# 2022-06-23_LN2_Autofill_Controller.net
KiCad netlist of a schematic drawn in EAGLE
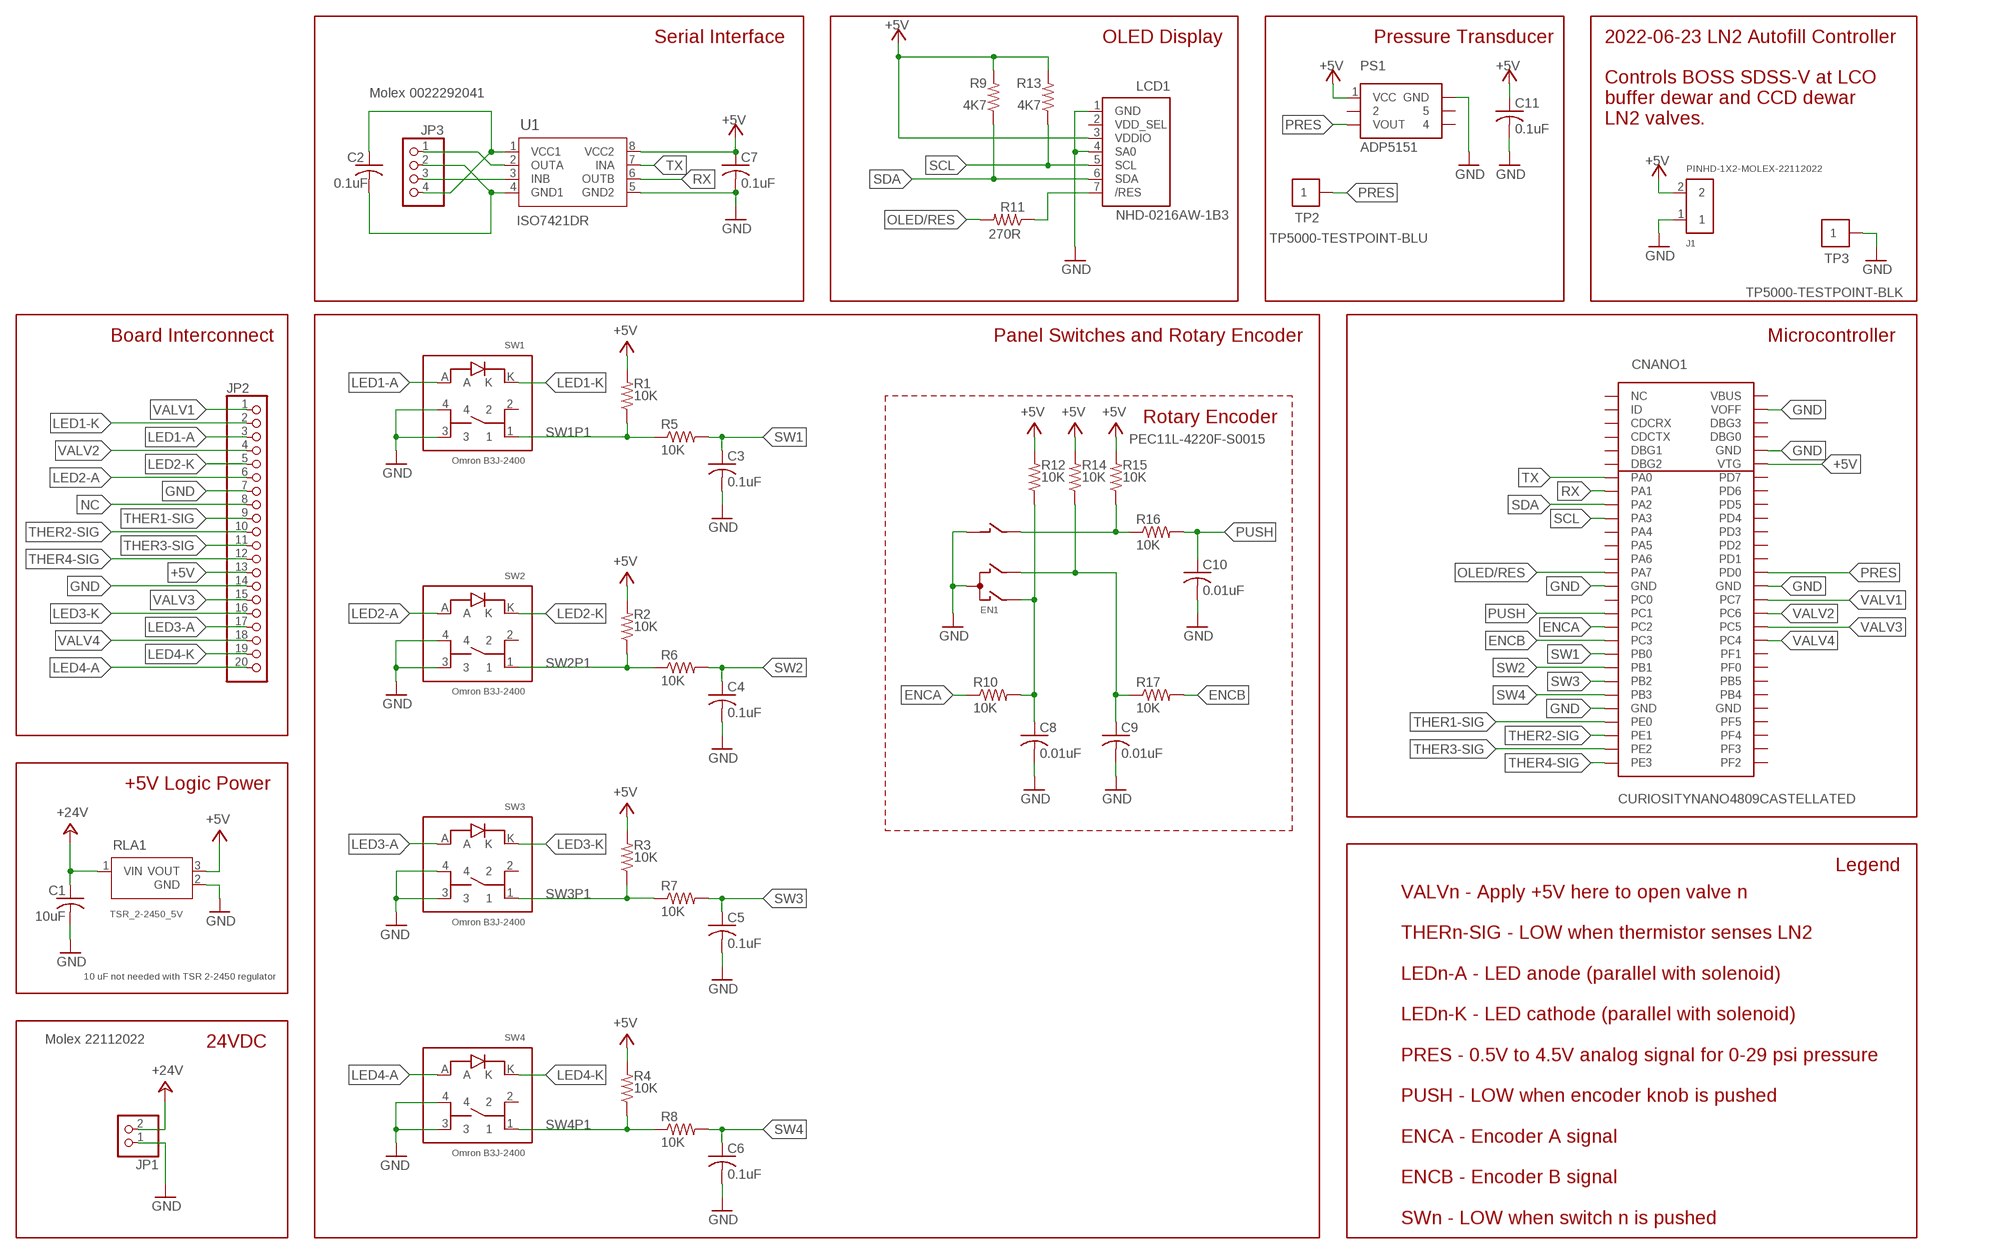
[diagram p0: schematic, sheet 1]

(export (version "E")
  (design (tool "Eeschema 10.0.6"))
  (components
    (comp (ref "C1")
      (value "10uF")
      (footprint "eagle-import:C1210K")
      (libsource (lib "eagle-import") (part "C-USC1210K"))
    )
    (comp (ref "C2")
      (value "0.1uF")
      (footprint "eagle-import:C0805")
      (libsource (lib "eagle-import") (part "C-USC0805"))
    )
    (comp (ref "C3")
      (value "0.1uF")
      (footprint "eagle-import:C0805")
      (libsource (lib "eagle-import") (part "C-USC0805"))
    )
    (comp (ref "C4")
      (value "0.1uF")
      (footprint "eagle-import:C0805")
      (libsource (lib "eagle-import") (part "C-USC0805"))
    )
    (comp (ref "C5")
      (value "0.1uF")
      (footprint "eagle-import:C0805")
      (libsource (lib "eagle-import") (part "C-USC0805"))
    )
    (comp (ref "C6")
      (value "0.1uF")
      (footprint "eagle-import:C0805")
      (libsource (lib "eagle-import") (part "C-USC0805"))
    )
    (comp (ref "C7")
      (value "0.1uF")
      (footprint "eagle-import:C0805")
      (libsource (lib "eagle-import") (part "C-USC0805"))
    )
    (comp (ref "C8")
      (value "0.01uF")
      (footprint "eagle-import:C0805")
      (libsource (lib "eagle-import") (part "C-USC0805"))
    )
    (comp (ref "C9")
      (value "0.01uF")
      (footprint "eagle-import:C0805")
      (libsource (lib "eagle-import") (part "C-USC0805"))
    )
    (comp (ref "C10")
      (value "0.01uF")
      (footprint "eagle-import:C0805")
      (libsource (lib "eagle-import") (part "C-USC0805"))
    )
    (comp (ref "C11")
      (value "0.1uF")
      (footprint "eagle-import:C0805")
      (libsource (lib "eagle-import") (part "C-USC0805"))
    )
    (comp (ref "CNANO1")
      (value "CURIOSITYNANO4809CASTELLATED")
      (footprint "eagle-import:CURIOSITYNANO4809CASTELLATED")
      (libsource (lib "eagle-import") (part "CURIOSITYNANO4809CASTELLATED"))
    )
    (comp (ref "EN1")
      (value "PEC11L-4220F-S0015")
      (footprint "eagle-import:ENC-BOURNES-PEC11L")
      (libsource (lib "eagle-import") (part "ENC-BOURNES-PEC11L"))
    )
    (comp (ref "J1")
      (value "PINHD-1X2-MOLEX-22112022")
      (footprint "eagle-import:1X02-MOLEX-22112022")
      (libsource (lib "eagle-import") (part "PINHD-1X2-MOLEX-22112022"))
    )
    (comp (ref "JP1")
      (value "Molex 22112022")
      (footprint "eagle-import:MOLEX-02-VERT")
      (libsource (lib "eagle-import") (part "PINHD-1X2MOLEX-02-VERT"))
    )
    (comp (ref "JP2")
      (value "PINHD-1X20")
      (footprint "eagle-import:1X20")
      (libsource (lib "eagle-import") (part "PINHD-1X20"))
    )
    (comp (ref "JP3")
      (value "Molex 0022292041")
      (footprint "eagle-import:MOLEX-04-VERT")
      (libsource (lib "eagle-import") (part "PINHD-1X4MOLEX-04-VERT"))
    )
    (comp (ref "LCD1")
      (value "NHD-0216AW-1B3")
      (footprint "eagle-import:LCD-NEWHAVEN-16X2")
      (libsource (lib "eagle-import") (part "LCD-NEWHAVEN-16X2"))
    )
    (comp (ref "PS1")
      (value "ADP5151")
      (footprint "eagle-import:PRESSURE-SENSOR-ADP5151")
      (libsource (lib "eagle-import") (part "PRESSURE-SENSOR-ADP5151"))
    )
    (comp (ref "R1")
      (value "10K")
      (footprint "eagle-import:R0805")
      (libsource (lib "eagle-import") (part "R-US_R0805"))
    )
    (comp (ref "R2")
      (value "10K")
      (footprint "eagle-import:R0805")
      (libsource (lib "eagle-import") (part "R-US_R0805"))
    )
    (comp (ref "R3")
      (value "10K")
      (footprint "eagle-import:R0805")
      (libsource (lib "eagle-import") (part "R-US_R0805"))
    )
    (comp (ref "R4")
      (value "10K")
      (footprint "eagle-import:R0805")
      (libsource (lib "eagle-import") (part "R-US_R0805"))
    )
    (comp (ref "R5")
      (value "10K")
      (footprint "eagle-import:R0805")
      (libsource (lib "eagle-import") (part "R-US_R0805"))
    )
    (comp (ref "R6")
      (value "10K")
      (footprint "eagle-import:R0805")
      (libsource (lib "eagle-import") (part "R-US_R0805"))
    )
    (comp (ref "R7")
      (value "10K")
      (footprint "eagle-import:R0805")
      (libsource (lib "eagle-import") (part "R-US_R0805"))
    )
    (comp (ref "R8")
      (value "10K")
      (footprint "eagle-import:R0805")
      (libsource (lib "eagle-import") (part "R-US_R0805"))
    )
    (comp (ref "R9")
      (value "4K7")
      (footprint "eagle-import:R0805")
      (libsource (lib "eagle-import") (part "R-US_R0805"))
    )
    (comp (ref "R10")
      (value "10K")
      (footprint "eagle-import:R0805")
      (libsource (lib "eagle-import") (part "R-US_R0805"))
    )
    (comp (ref "R11")
      (value "270R")
      (footprint "eagle-import:R0805")
      (libsource (lib "eagle-import") (part "R-US_R0805"))
    )
    (comp (ref "R12")
      (value "10K")
      (footprint "eagle-import:R0805")
      (libsource (lib "eagle-import") (part "R-US_R0805"))
    )
    (comp (ref "R13")
      (value "4K7")
      (footprint "eagle-import:R0805")
      (libsource (lib "eagle-import") (part "R-US_R0805"))
    )
    (comp (ref "R14")
      (value "10K")
      (footprint "eagle-import:R0805")
      (libsource (lib "eagle-import") (part "R-US_R0805"))
    )
    (comp (ref "R15")
      (value "10K")
      (footprint "eagle-import:R0805")
      (libsource (lib "eagle-import") (part "R-US_R0805"))
    )
    (comp (ref "R16")
      (value "10K")
      (footprint "eagle-import:R0805")
      (libsource (lib "eagle-import") (part "R-US_R0805"))
    )
    (comp (ref "R17")
      (value "10K")
      (footprint "eagle-import:R0805")
      (libsource (lib "eagle-import") (part "R-US_R0805"))
    )
    (comp (ref "RLA1")
      (value "TSR_2-2450_5V")
      (footprint "eagle-import:TSR2-SINGLE_TRP")
      (fields
        (field (name "MANUFACTURER_PART_NUMBER") "TSR 2-2450")
        (field (name "COPYRIGHT") "Copyright (C) 2022 Ultra Librarian. All rights reserved.")
      )
      (libsource (lib "eagle-import") (part "TSR_2-2450_5V_REGULATOR"))
    )
    (comp (ref "SW1")
      (value "Omron B3J-2400")
      (footprint "eagle-import:SWITCH-OMRON-B3J-1LED")
      (libsource (lib "eagle-import") (part "SWITCH-OMRON-B3J-1LED"))
    )
    (comp (ref "SW2")
      (value "Omron B3J-2400")
      (footprint "eagle-import:SWITCH-OMRON-B3J-1LED")
      (libsource (lib "eagle-import") (part "SWITCH-OMRON-B3J-1LED"))
    )
    (comp (ref "SW3")
      (value "Omron B3J-2400")
      (footprint "eagle-import:SWITCH-OMRON-B3J-1LED")
      (libsource (lib "eagle-import") (part "SWITCH-OMRON-B3J-1LED"))
    )
    (comp (ref "SW4")
      (value "Omron B3J-2400")
      (footprint "eagle-import:SWITCH-OMRON-B3J-1LED")
      (libsource (lib "eagle-import") (part "SWITCH-OMRON-B3J-1LED"))
    )
    (comp (ref "TP2")
      (value "TP5000-TESTPOINT-BLU")
      (footprint "eagle-import:TP5000-TESTPOINT-BLU")
      (libsource (lib "eagle-import") (part "TP5000-TESTPOINT-BLU"))
    )
    (comp (ref "TP3")
      (value "TP5000-TESTPOINT-BLK")
      (footprint "eagle-import:TP5000-TESTPOINT-BLK")
      (libsource (lib "eagle-import") (part "TP5000-TESTPOINT-BLK"))
    )
    (comp (ref "U1")
      (value "ISO7421DR")
      (footprint "eagle-import:SOIC127P599X175-8N")
      (libsource (lib "eagle-import") (part "ISO7421DRTI-SOIC-D8"))
    )
  )
  (nets
    (net (code "1") (name "+5V") (class "Default")
      (node (ref "C11") (pin "1") (pinfunction "1_1") (pintype "passive"))
      (node (ref "C7") (pin "1") (pinfunction "1_1") (pintype "passive"))
      (node (ref "CNANO1") (pin "VTG") (pinfunction "VTG_VTG") (pintype "bidirectional"))
      (node (ref "J1") (pin "2") (pinfunction "2_2") (pintype "bidirectional"))
      (node (ref "JP2") (pin "13") (pinfunction "13_13") (pintype "passive"))
      (node (ref "LCD1") (pin "3") (pinfunction "VDDIO_3") (pintype "bidirectional"))
      (node (ref "PS1") (pin "1") (pinfunction "VCC_1") (pintype "bidirectional"))
      (node (ref "R1") (pin "2") (pinfunction "2_2") (pintype "passive"))
      (node (ref "R12") (pin "2") (pinfunction "2_2") (pintype "passive"))
      (node (ref "R13") (pin "2") (pinfunction "2_2") (pintype "passive"))
      (node (ref "R14") (pin "2") (pinfunction "2_2") (pintype "passive"))
      (node (ref "R15") (pin "2") (pinfunction "2_2") (pintype "passive"))
      (node (ref "R2") (pin "2") (pinfunction "2_2") (pintype "passive"))
      (node (ref "R3") (pin "2") (pinfunction "2_2") (pintype "passive"))
      (node (ref "R4") (pin "2") (pinfunction "2_2") (pintype "passive"))
      (node (ref "R9") (pin "2") (pinfunction "2_2") (pintype "passive"))
      (node (ref "RLA1") (pin "3") (pinfunction "VOUT_3") (pintype "passive"))
      (node (ref "U1") (pin "8") (pinfunction "VCC2_8") (pintype "power_in"))
    )
    (net (code "2") (name "+24V") (class "Default")
      (node (ref "C1") (pin "1") (pinfunction "1_1") (pintype "passive"))
      (node (ref "JP1") (pin "2") (pinfunction "2_2") (pintype "passive"))
      (node (ref "RLA1") (pin "1") (pinfunction "VIN_1") (pintype "passive"))
    )
    (net (code "3") (name "/SW1P1") (class "Default")
      (node (ref "R1") (pin "1") (pinfunction "1_1") (pintype "passive"))
      (node (ref "R5") (pin "1") (pinfunction "1_1") (pintype "passive"))
      (node (ref "SW1") (pin "1") (pinfunction "1_1") (pintype "bidirectional"))
    )
    (net (code "4") (name "/SW2P1") (class "Default")
      (node (ref "R2") (pin "1") (pinfunction "1_1") (pintype "passive"))
      (node (ref "R6") (pin "1") (pinfunction "1_1") (pintype "passive"))
      (node (ref "SW2") (pin "1") (pinfunction "1_1") (pintype "bidirectional"))
    )
    (net (code "5") (name "/SW3P1") (class "Default")
      (node (ref "R3") (pin "1") (pinfunction "1_1") (pintype "passive"))
      (node (ref "R7") (pin "1") (pinfunction "1_1") (pintype "passive"))
      (node (ref "SW3") (pin "1") (pinfunction "1_1") (pintype "bidirectional"))
    )
    (net (code "6") (name "/SW4P1") (class "Default")
      (node (ref "R4") (pin "1") (pinfunction "1_1") (pintype "passive"))
      (node (ref "R8") (pin "1") (pinfunction "1_1") (pintype "passive"))
      (node (ref "SW4") (pin "1") (pinfunction "1_1") (pintype "bidirectional"))
    )
    (net (code "7") (name "ENCA") (class "Default")
      (node (ref "CNANO1") (pin "PC2") (pinfunction "PC2_PC2") (pintype "bidirectional"))
      (node (ref "R10") (pin "1") (pinfunction "1_1") (pintype "passive"))
    )
    (net (code "8") (name "ENCB") (class "Default")
      (node (ref "CNANO1") (pin "PC3") (pinfunction "PC3_PC3") (pintype "bidirectional"))
      (node (ref "R17") (pin "2") (pinfunction "2_2") (pintype "passive"))
    )
    (net (code "9") (name "GND") (class "Default")
      (node (ref "C1") (pin "2") (pinfunction "2_2") (pintype "passive"))
      (node (ref "C10") (pin "2") (pinfunction "2_2") (pintype "passive"))
      (node (ref "C11") (pin "2") (pinfunction "2_2") (pintype "passive"))
      (node (ref "C3") (pin "2") (pinfunction "2_2") (pintype "passive"))
      (node (ref "C4") (pin "2") (pinfunction "2_2") (pintype "passive"))
      (node (ref "C5") (pin "2") (pinfunction "2_2") (pintype "passive"))
      (node (ref "C6") (pin "2") (pinfunction "2_2") (pintype "passive"))
      (node (ref "C7") (pin "2") (pinfunction "2_2") (pintype "passive"))
      (node (ref "C8") (pin "2") (pinfunction "2_2") (pintype "passive"))
      (node (ref "C9") (pin "2") (pinfunction "2_2") (pintype "passive"))
      (node (ref "CNANO1") (pin "GND15") (pinfunction "GND_GND15") (pintype "bidirectional"))
      (node (ref "CNANO1") (pin "GND24") (pinfunction "GND_GND24") (pintype "bidirectional"))
      (node (ref "CNANO1") (pin "GND42") (pinfunction "GND_GND42") (pintype "bidirectional"))
      (node (ref "CNANO1") (pin "GND52") (pinfunction "GND_GND52") (pintype "bidirectional"))
      (node (ref "CNANO1") (pin "VOFF") (pinfunction "VOFF_VOFF") (pintype "bidirectional"))
      (node (ref "EN1") (pin "2") (pinfunction "C1_2") (pintype "passive"))
      (node (ref "EN1") (pin "C") (pinfunction "C_C") (pintype "passive"))
      (node (ref "J1") (pin "1") (pinfunction "1_1") (pintype "bidirectional"))
      (node (ref "JP1") (pin "1") (pinfunction "1_1") (pintype "passive"))
      (node (ref "JP2") (pin "14") (pinfunction "14_14") (pintype "passive"))
      (node (ref "JP2") (pin "7") (pinfunction "7_7") (pintype "passive"))
      (node (ref "LCD1") (pin "1") (pinfunction "GND_1") (pintype "bidirectional"))
      (node (ref "LCD1") (pin "4") (pinfunction "SA0_4") (pintype "bidirectional"))
      (node (ref "PS1") (pin "6") (pinfunction "GND_6") (pintype "bidirectional"))
      (node (ref "RLA1") (pin "2") (pinfunction "GND_2") (pintype "passive"))
      (node (ref "SW1") (pin "3") (pinfunction "3_3") (pintype "bidirectional"))
      (node (ref "SW1") (pin "4") (pinfunction "4_4") (pintype "bidirectional"))
      (node (ref "SW2") (pin "3") (pinfunction "3_3") (pintype "bidirectional"))
      (node (ref "SW2") (pin "4") (pinfunction "4_4") (pintype "bidirectional"))
      (node (ref "SW3") (pin "3") (pinfunction "3_3") (pintype "bidirectional"))
      (node (ref "SW3") (pin "4") (pinfunction "4_4") (pintype "bidirectional"))
      (node (ref "SW4") (pin "3") (pinfunction "3_3") (pintype "bidirectional"))
      (node (ref "SW4") (pin "4") (pinfunction "4_4") (pintype "bidirectional"))
      (node (ref "TP3") (pin "P$1") (pinfunction "1_P$1") (pintype "bidirectional"))
      (node (ref "U1") (pin "5") (pinfunction "GND2_5") (pintype "power_in"))
    )
    (net (code "10") (name "LED1-A") (class "Default")
      (node (ref "JP2") (pin "3") (pinfunction "3_3") (pintype "passive"))
      (node (ref "SW1") (pin "A") (pinfunction "A_A") (pintype "bidirectional"))
    )
    (net (code "11") (name "LED1-K") (class "Default")
      (node (ref "JP2") (pin "2") (pinfunction "2_2") (pintype "passive"))
      (node (ref "SW1") (pin "K") (pinfunction "K_K") (pintype "bidirectional"))
    )
    (net (code "12") (name "LED2-A") (class "Default")
      (node (ref "JP2") (pin "6") (pinfunction "6_6") (pintype "passive"))
      (node (ref "SW2") (pin "A") (pinfunction "A_A") (pintype "bidirectional"))
    )
    (net (code "13") (name "LED2-K") (class "Default")
      (node (ref "JP2") (pin "5") (pinfunction "5_5") (pintype "passive"))
      (node (ref "SW2") (pin "K") (pinfunction "K_K") (pintype "bidirectional"))
    )
    (net (code "14") (name "LED3-A") (class "Default")
      (node (ref "JP2") (pin "17") (pinfunction "17_17") (pintype "passive"))
      (node (ref "SW3") (pin "A") (pinfunction "A_A") (pintype "bidirectional"))
    )
    (net (code "15") (name "LED3-K") (class "Default")
      (node (ref "JP2") (pin "16") (pinfunction "16_16") (pintype "passive"))
      (node (ref "SW3") (pin "K") (pinfunction "K_K") (pintype "bidirectional"))
    )
    (net (code "16") (name "LED4-A") (class "Default")
      (node (ref "JP2") (pin "20") (pinfunction "20_20") (pintype "passive"))
      (node (ref "SW4") (pin "A") (pinfunction "A_A") (pintype "bidirectional"))
    )
    (net (code "17") (name "LED4-K") (class "Default")
      (node (ref "JP2") (pin "19") (pinfunction "19_19") (pintype "passive"))
      (node (ref "SW4") (pin "K") (pinfunction "K_K") (pintype "bidirectional"))
    )
    (net (code "18") (name "NC") (class "Default")
      (node (ref "JP2") (pin "8") (pinfunction "8_8") (pintype "passive"))
    )
    (net (code "19") (name "Net-(C8-Pad1)") (class "Default")
      (node (ref "C8") (pin "1") (pinfunction "1_1") (pintype "passive"))
      (node (ref "EN1") (pin "A") (pinfunction "A_A") (pintype "passive"))
      (node (ref "R10") (pin "2") (pinfunction "2_2") (pintype "passive"))
      (node (ref "R12") (pin "1") (pinfunction "1_1") (pintype "passive"))
    )
    (net (code "20") (name "Net-(C9-Pad1)") (class "Default")
      (node (ref "C9") (pin "1") (pinfunction "1_1") (pintype "passive"))
      (node (ref "EN1") (pin "B") (pinfunction "B_B") (pintype "passive"))
      (node (ref "R14") (pin "1") (pinfunction "1_1") (pintype "passive"))
      (node (ref "R17") (pin "1") (pinfunction "1_1") (pintype "passive"))
    )
    (net (code "21") (name "Net-(EN1-B1)") (class "Default")
      (node (ref "EN1") (pin "1") (pinfunction "B1_1") (pintype "passive"))
      (node (ref "R15") (pin "1") (pinfunction "1_1") (pintype "passive"))
      (node (ref "R16") (pin "1") (pinfunction "1_1") (pintype "passive"))
    )
    (net (code "22") (name "Net-(LCD1-{slash}RES)") (class "Default")
      (node (ref "LCD1") (pin "7") (pinfunction "/RES_7") (pintype "bidirectional"))
      (node (ref "R11") (pin "1") (pinfunction "1_1") (pintype "passive"))
    )
    (net (code "23") (name "Net-(U1-GND1)") (class "Default")
      (node (ref "C2") (pin "2") (pinfunction "2_2") (pintype "passive"))
      (node (ref "JP3") (pin "2") (pinfunction "2_2") (pintype "passive"))
      (node (ref "U1") (pin "4") (pinfunction "GND1_4") (pintype "power_in"))
    )
    (net (code "24") (name "Net-(U1-INB)") (class "Default")
      (node (ref "JP3") (pin "3") (pinfunction "3_3") (pintype "passive"))
      (node (ref "U1") (pin "3") (pinfunction "INB_3") (pintype "input"))
    )
    (net (code "25") (name "Net-(U1-OUTA)") (class "Default")
      (node (ref "JP3") (pin "1") (pinfunction "1_1") (pintype "passive"))
      (node (ref "U1") (pin "2") (pinfunction "OUTA_2") (pintype "output"))
    )
    (net (code "26") (name "Net-(U1-VCC1)") (class "Default")
      (node (ref "C2") (pin "1") (pinfunction "1_1") (pintype "passive"))
      (node (ref "JP3") (pin "4") (pinfunction "4_4") (pintype "passive"))
      (node (ref "U1") (pin "1") (pinfunction "VCC1_1") (pintype "power_in"))
    )
    (net (code "27") (name "OLED{slash}RES") (class "Default")
      (node (ref "CNANO1") (pin "PA7-SS") (pinfunction "PA7_PA7-SS") (pintype "bidirectional"))
      (node (ref "R11") (pin "2") (pinfunction "2_2") (pintype "passive"))
    )
    (net (code "28") (name "PRES") (class "Default")
      (node (ref "CNANO1") (pin "PD0-AIN0") (pinfunction "PD0_PD0-AIN0") (pintype "bidirectional"))
      (node (ref "PS1") (pin "3") (pinfunction "VOUT_3") (pintype "bidirectional"))
      (node (ref "TP2") (pin "P$1") (pinfunction "1_P$1") (pintype "bidirectional"))
    )
    (net (code "29") (name "PUSH") (class "Default")
      (node (ref "C10") (pin "1") (pinfunction "1_1") (pintype "passive"))
      (node (ref "CNANO1") (pin "PC1-RX") (pinfunction "PC1_PC1-RX") (pintype "bidirectional"))
      (node (ref "R16") (pin "2") (pinfunction "2_2") (pintype "passive"))
    )
    (net (code "30") (name "RX") (class "Default")
      (node (ref "CNANO1") (pin "PA1-RX") (pinfunction "PA1_PA1-RX") (pintype "bidirectional"))
      (node (ref "U1") (pin "6") (pinfunction "OUTB_6") (pintype "output"))
    )
    (net (code "31") (name "SCL") (class "Default")
      (node (ref "CNANO1") (pin "PA3-SCL") (pinfunction "PA3_PA3-SCL") (pintype "bidirectional"))
      (node (ref "LCD1") (pin "5") (pinfunction "SCL_5") (pintype "bidirectional"))
      (node (ref "R13") (pin "1") (pinfunction "1_1") (pintype "passive"))
    )
    (net (code "32") (name "SDA") (class "Default")
      (node (ref "CNANO1") (pin "PA2-SDA") (pinfunction "PA2_PA2-SDA") (pintype "bidirectional"))
      (node (ref "LCD1") (pin "6") (pinfunction "SDA_6") (pintype "bidirectional"))
      (node (ref "R9") (pin "1") (pinfunction "1_1") (pintype "passive"))
    )
    (net (code "33") (name "SW1") (class "Default")
      (node (ref "C3") (pin "1") (pinfunction "1_1") (pintype "passive"))
      (node (ref "CNANO1") (pin "PB0-TX") (pinfunction "PB0_PB0-TX") (pintype "bidirectional"))
      (node (ref "R5") (pin "2") (pinfunction "2_2") (pintype "passive"))
    )
    (net (code "34") (name "SW2") (class "Default")
      (node (ref "C4") (pin "1") (pinfunction "1_1") (pintype "passive"))
      (node (ref "CNANO1") (pin "PB1-RX") (pinfunction "PB1_PB1-RX") (pintype "bidirectional"))
      (node (ref "R6") (pin "2") (pinfunction "2_2") (pintype "passive"))
    )
    (net (code "35") (name "SW3") (class "Default")
      (node (ref "C5") (pin "1") (pinfunction "1_1") (pintype "passive"))
      (node (ref "CNANO1") (pin "PB2") (pinfunction "PB2_PB2") (pintype "bidirectional"))
      (node (ref "R7") (pin "2") (pinfunction "2_2") (pintype "passive"))
    )
    (net (code "36") (name "SW4") (class "Default")
      (node (ref "C6") (pin "1") (pinfunction "1_1") (pintype "passive"))
      (node (ref "CNANO1") (pin "PB3") (pinfunction "PB3_PB3") (pintype "bidirectional"))
      (node (ref "R8") (pin "2") (pinfunction "2_2") (pintype "passive"))
    )
    (net (code "37") (name "THER1-SIG") (class "Default")
      (node (ref "CNANO1") (pin "PE0") (pinfunction "PE0_PE0") (pintype "bidirectional"))
      (node (ref "JP2") (pin "9") (pinfunction "9_9") (pintype "passive"))
    )
    (net (code "38") (name "THER2-SIG") (class "Default")
      (node (ref "CNANO1") (pin "PE1") (pinfunction "PE1_PE1") (pintype "bidirectional"))
      (node (ref "JP2") (pin "10") (pinfunction "10_10") (pintype "passive"))
    )
    (net (code "39") (name "THER3-SIG") (class "Default")
      (node (ref "CNANO1") (pin "PE2") (pinfunction "PE2_PE2") (pintype "bidirectional"))
      (node (ref "JP2") (pin "11") (pinfunction "11_11") (pintype "passive"))
    )
    (net (code "40") (name "THER4-SIG") (class "Default")
      (node (ref "CNANO1") (pin "PE3") (pinfunction "PE3_PE3") (pintype "bidirectional"))
      (node (ref "JP2") (pin "12") (pinfunction "12_12") (pintype "passive"))
    )
    (net (code "41") (name "TX") (class "Default")
      (node (ref "CNANO1") (pin "PA0-TX") (pinfunction "PA0_PA0-TX") (pintype "bidirectional"))
      (node (ref "U1") (pin "7") (pinfunction "INA_7") (pintype "input"))
    )
    (net (code "42") (name "VALV1") (class "Default")
      (node (ref "CNANO1") (pin "PC7") (pinfunction "PC7_PC7") (pintype "bidirectional"))
      (node (ref "JP2") (pin "1") (pinfunction "1_1") (pintype "passive"))
    )
    (net (code "43") (name "VALV2") (class "Default")
      (node (ref "CNANO1") (pin "PC6") (pinfunction "PC6_PC6") (pintype "bidirectional"))
      (node (ref "JP2") (pin "4") (pinfunction "4_4") (pintype "passive"))
    )
    (net (code "44") (name "VALV3") (class "Default")
      (node (ref "CNANO1") (pin "PC5") (pinfunction "PC5_PC5") (pintype "bidirectional"))
      (node (ref "JP2") (pin "15") (pinfunction "15_15") (pintype "passive"))
    )
    (net (code "45") (name "VALV4") (class "Default")
      (node (ref "CNANO1") (pin "PC4") (pinfunction "PC4_PC4") (pintype "bidirectional"))
      (node (ref "JP2") (pin "18") (pinfunction "18_18") (pintype "passive"))
    )
    (net (code "46") (name "unconnected-(CNANO1-CDCRX-PadPB0-RX)") (class "Default")
      (node (ref "CNANO1") (pin "PB0-RX") (pinfunction "CDCRX_PB0-RX") (pintype "bidirectional"))
    )
    (net (code "47") (name "unconnected-(CNANO1-CDCTX-PadPB1-TX)") (class "Default")
      (node (ref "CNANO1") (pin "PB1-TX") (pinfunction "CDCTX_PB1-TX") (pintype "bidirectional"))
    )
    (net (code "48") (name "unconnected-(CNANO1-DBG0-PadUPDI)") (class "Default")
      (node (ref "CNANO1") (pin "UPDI") (pinfunction "DBG0_UPDI") (pintype "bidirectional"))
    )
    (net (code "49") (name "unconnected-(CNANO1-DBG1-PadPF3-5)") (class "Default")
      (node (ref "CNANO1") (pin "PF3-5") (pinfunction "DBG1_PF3-5") (pintype "bidirectional"))
    )
    (net (code "50") (name "unconnected-(CNANO1-DBG2-PadPF2-6)") (class "Default")
      (node (ref "CNANO1") (pin "PF2-6") (pinfunction "DBG2_PF2-6") (pintype "bidirectional"))
    )
    (net (code "51") (name "unconnected-(CNANO1-DBG3-PadPF6-SW0)") (class "Default")
      (node (ref "CNANO1") (pin "PF6-SW0") (pinfunction "DBG3_PF6-SW0") (pintype "bidirectional"))
    )
    (net (code "52") (name "unconnected-(CNANO1-GND-PadGND33)") (class "Default")
      (node (ref "CNANO1") (pin "GND33") (pinfunction "GND_GND33") (pintype "bidirectional"))
    )
    (net (code "53") (name "unconnected-(CNANO1-PA4-PadPA4-MOSI)") (class "Default")
      (node (ref "CNANO1") (pin "PA4-MOSI") (pinfunction "PA4_PA4-MOSI") (pintype "bidirectional"))
    )
    (net (code "54") (name "unconnected-(CNANO1-PA5-PadPA5-MISO)") (class "Default")
      (node (ref "CNANO1") (pin "PA5-MISO") (pinfunction "PA5_PA5-MISO") (pintype "bidirectional"))
    )
    (net (code "55") (name "unconnected-(CNANO1-PA6-PadPA6-SCK)") (class "Default")
      (node (ref "CNANO1") (pin "PA6-SCK") (pinfunction "PA6_PA6-SCK") (pintype "bidirectional"))
    )
    (net (code "56") (name "unconnected-(CNANO1-PC0-PadPC0-TX)") (class "Default")
      (node (ref "CNANO1") (pin "PC0-TX") (pinfunction "PC0_PC0-TX") (pintype "bidirectional"))
    )
    (net (code "57") (name "unconnected-(CNANO1-PD1-PadPD1-AIN1)") (class "Default")
      (node (ref "CNANO1") (pin "PD1-AIN1") (pinfunction "PD1_PD1-AIN1") (pintype "bidirectional"))
    )
    (net (code "58") (name "unconnected-(CNANO1-PD2-PadPD2-AIN2)") (class "Default")
      (node (ref "CNANO1") (pin "PD2-AIN2") (pinfunction "PD2_PD2-AIN2") (pintype "bidirectional"))
    )
    (net (code "59") (name "unconnected-(CNANO1-PD3-PadPD3-AIN3)") (class "Default")
      (node (ref "CNANO1") (pin "PD3-AIN3") (pinfunction "PD3_PD3-AIN3") (pintype "bidirectional"))
    )
    (net (code "60") (name "unconnected-(CNANO1-PD4-PadPD4-AIN4)") (class "Default")
      (node (ref "CNANO1") (pin "PD4-AIN4") (pinfunction "PD4_PD4-AIN4") (pintype "bidirectional"))
    )
    (net (code "61") (name "unconnected-(CNANO1-PD5-PadPD5-AIN5)") (class "Default")
      (node (ref "CNANO1") (pin "PD5-AIN5") (pinfunction "PD5_PD5-AIN5") (pintype "bidirectional"))
    )
    (net (code "62") (name "unconnected-(CNANO1-PD6-PadPD6-AIN6)") (class "Default")
      (node (ref "CNANO1") (pin "PD6-AIN6") (pinfunction "PD6_PD6-AIN6") (pintype "bidirectional"))
    )
    (net (code "63") (name "unconnected-(CNANO1-PD7-PadPD7-AIN7)") (class "Default")
      (node (ref "CNANO1") (pin "PD7-AIN7") (pinfunction "PD7_PD7-AIN7") (pintype "bidirectional"))
    )
    (net (code "64") (name "unconnected-(CNANO1-PF0-PadPF0-TOSC1)") (class "Default")
      (node (ref "CNANO1") (pin "PF0-TOSC1") (pinfunction "PF0_PF0-TOSC1") (pintype "bidirectional"))
    )
    (net (code "65") (name "unconnected-(CNANO1-PF1-PadPF1-TOSC2)") (class "Default")
      (node (ref "CNANO1") (pin "PF1-TOSC2") (pinfunction "PF1_PF1-TOSC2") (pintype "bidirectional"))
    )
    (net (code "66") (name "unconnected-(CNANO1-PF5-PadPF5-LED)") (class "Default")
      (node (ref "CNANO1") (pin "PF5-LED") (pinfunction "PF5_PF5-LED") (pintype "bidirectional"))
    )
    (net (code "67") (name "unconnected-(CNANO1-PadID)") (class "Default")
      (node (ref "CNANO1") (pin "ID") (pinfunction "ID_ID") (pintype "bidirectional"))
    )
    (net (code "68") (name "unconnected-(CNANO1-PadNC)") (class "Default")
      (node (ref "CNANO1") (pin "NC") (pinfunction "NC_NC") (pintype "bidirectional"))
    )
    (net (code "69") (name "unconnected-(CNANO1-PadPB4)") (class "Default")
      (node (ref "CNANO1") (pin "PB4") (pinfunction "PB4_PB4") (pintype "bidirectional"))
    )
    (net (code "70") (name "unconnected-(CNANO1-PadPB5)") (class "Default")
      (node (ref "CNANO1") (pin "PB5") (pinfunction "PB5_PB5") (pintype "bidirectional"))
    )
    (net (code "71") (name "unconnected-(CNANO1-PadPF2)") (class "Default")
      (node (ref "CNANO1") (pin "PF2") (pinfunction "PF2_PF2") (pintype "bidirectional"))
    )
    (net (code "72") (name "unconnected-(CNANO1-PadPF3)") (class "Default")
      (node (ref "CNANO1") (pin "PF3") (pinfunction "PF3_PF3") (pintype "bidirectional"))
    )
    (net (code "73") (name "unconnected-(CNANO1-PadPF4)") (class "Default")
      (node (ref "CNANO1") (pin "PF4") (pinfunction "PF4_PF4") (pintype "bidirectional"))
    )
    (net (code "74") (name "unconnected-(CNANO1-PadVBUS)") (class "Default")
      (node (ref "CNANO1") (pin "VBUS") (pinfunction "VBUS_VBUS") (pintype "bidirectional"))
    )
    (net (code "75") (name "unconnected-(LCD1-VDD_SEL-Pad2)") (class "Default")
      (node (ref "LCD1") (pin "2") (pinfunction "VDD_SEL_2") (pintype "bidirectional"))
    )
    (net (code "76") (name "unconnected-(PS1-Pad2)") (class "Default")
      (node (ref "PS1") (pin "2") (pinfunction "2_2") (pintype "bidirectional"))
    )
    (net (code "77") (name "unconnected-(PS1-Pad4)") (class "Default")
      (node (ref "PS1") (pin "4") (pinfunction "4_4") (pintype "bidirectional"))
    )
    (net (code "78") (name "unconnected-(PS1-Pad5)") (class "Default")
      (node (ref "PS1") (pin "5") (pinfunction "5_5") (pintype "bidirectional"))
    )
    (net (code "79") (name "unconnected-(SW1-Pad2)") (class "Default")
      (node (ref "SW1") (pin "2") (pinfunction "2_2") (pintype "bidirectional"))
    )
    (net (code "80") (name "unconnected-(SW2-Pad2)") (class "Default")
      (node (ref "SW2") (pin "2") (pinfunction "2_2") (pintype "bidirectional"))
    )
    (net (code "81") (name "unconnected-(SW3-Pad2)") (class "Default")
      (node (ref "SW3") (pin "2") (pinfunction "2_2") (pintype "bidirectional"))
    )
    (net (code "82") (name "unconnected-(SW4-Pad2)") (class "Default")
      (node (ref "SW4") (pin "2") (pinfunction "2_2") (pintype "bidirectional"))
    )
  )
)
